# hvreg_feedback_2PS_FS.net
KiCad netlist of a schematic drawn in EAGLE
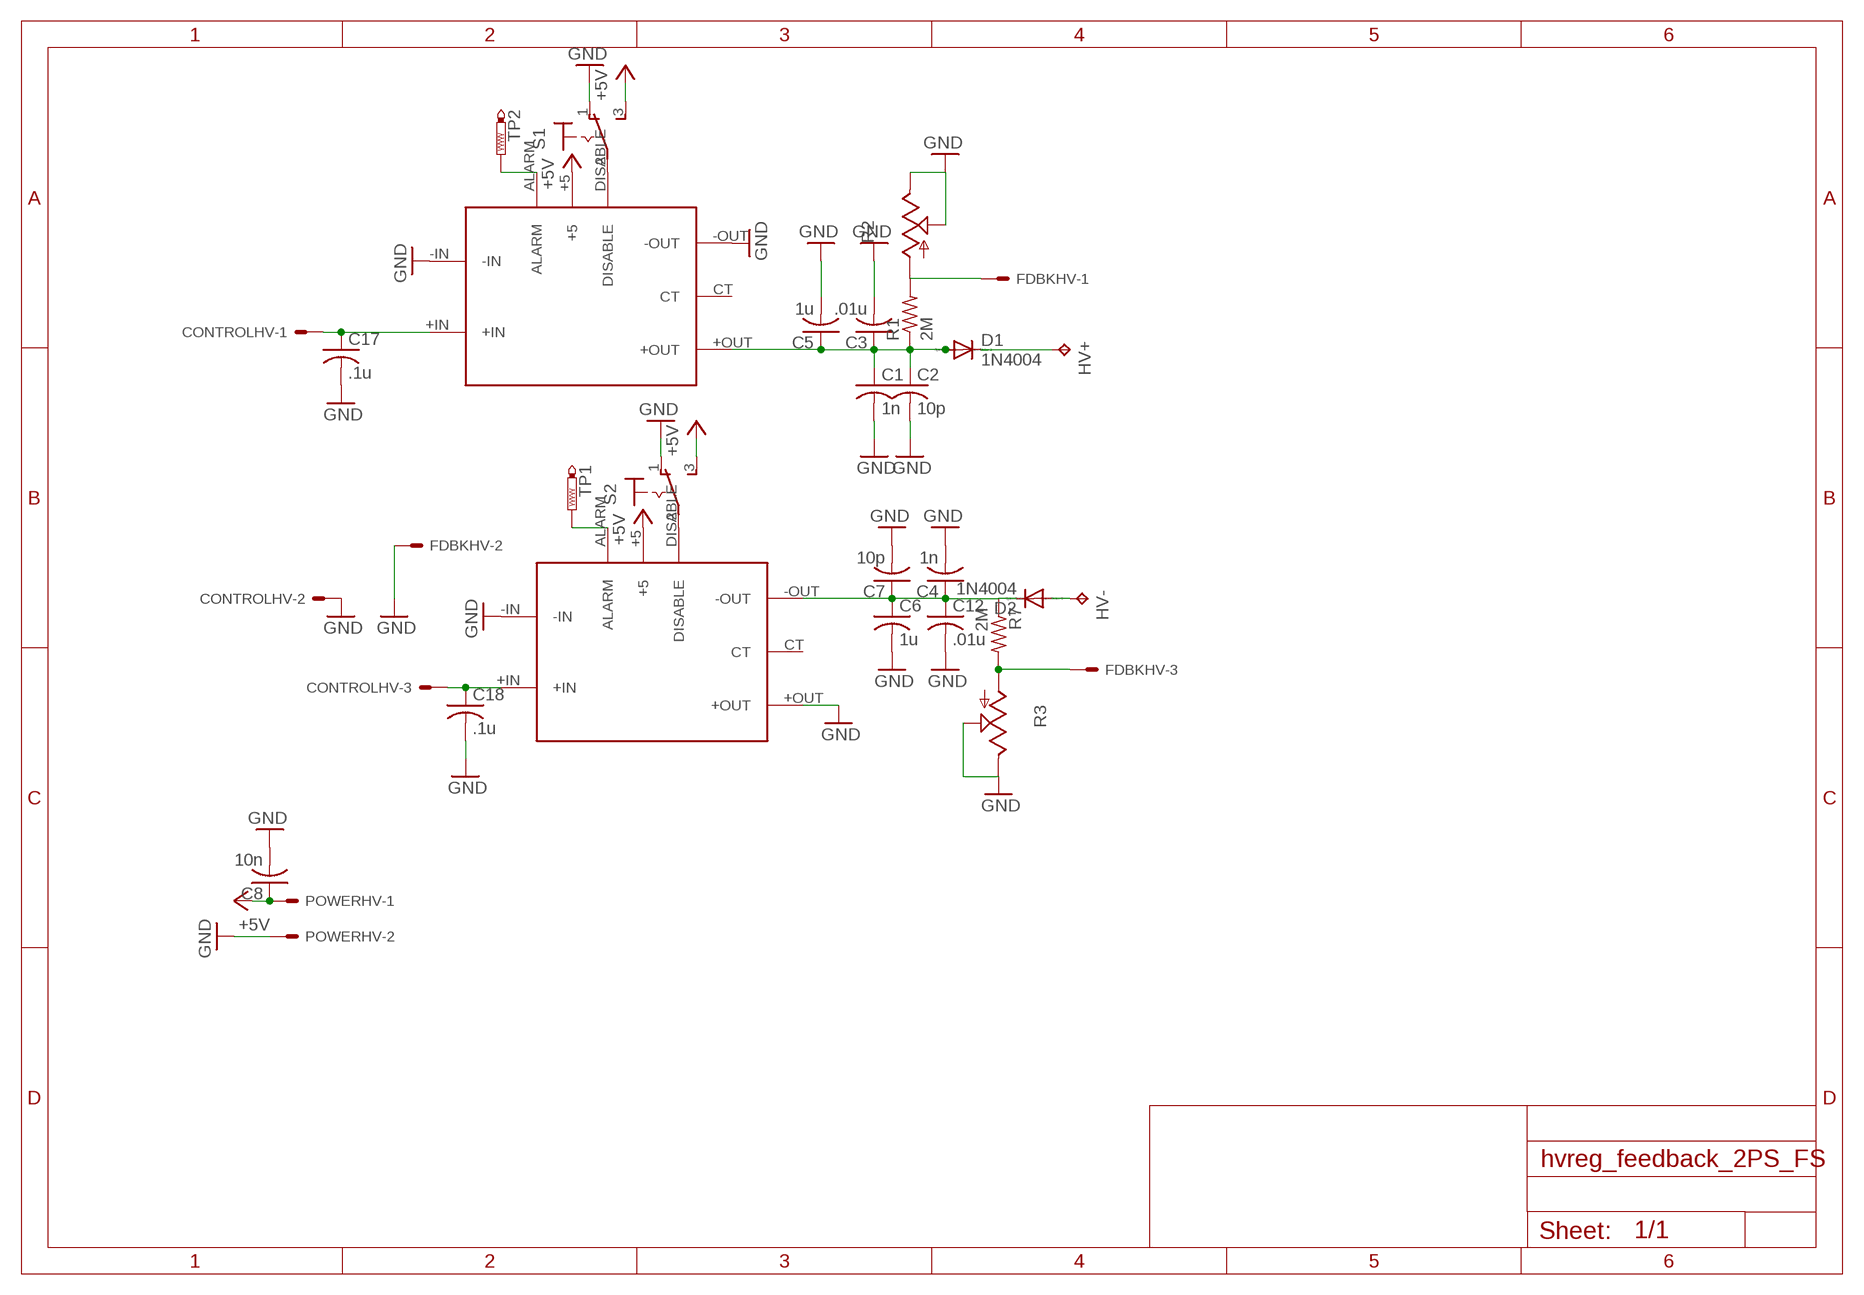
[diagram p0: schematic, sheet 1]

(export (version "E")
  (design (tool "Eeschema 10.0.6"))
  (components
    (comp (ref "C1")
      (value "1n")
      (footprint "eagle-import:C102-043X133")
      (libsource (lib "eagle-import") (part "C-US102-043X133"))
    )
    (comp (ref "C2")
      (value "10p")
      (footprint "eagle-import:C102-043X133")
      (libsource (lib "eagle-import") (part "C-US102-043X133"))
    )
    (comp (ref "C3")
      (value ".01u")
      (footprint "eagle-import:C102-043X133")
      (libsource (lib "eagle-import") (part "C-US102-043X133"))
    )
    (comp (ref "C4")
      (value "1n")
      (footprint "eagle-import:C102-043X133")
      (libsource (lib "eagle-import") (part "C-US102-043X133"))
    )
    (comp (ref "C5")
      (value "1u")
      (footprint "eagle-import:C275-205X316")
      (libsource (lib "eagle-import") (part "C-US275-205X316"))
    )
    (comp (ref "C6")
      (value "1u")
      (footprint "eagle-import:C275-205X316")
      (libsource (lib "eagle-import") (part "C-US275-205X316"))
    )
    (comp (ref "C7")
      (value "10p")
      (footprint "eagle-import:C102-043X133")
      (libsource (lib "eagle-import") (part "C-US102-043X133"))
    )
    (comp (ref "C8")
      (value "10n")
      (footprint "eagle-import:C050-024X044")
      (libsource (lib "eagle-import") (part "C-US050-024X044"))
    )
    (comp (ref "C12")
      (value ".01u")
      (footprint "eagle-import:C102-043X133")
      (libsource (lib "eagle-import") (part "C-US102-043X133"))
    )
    (comp (ref "C17")
      (value ".1u")
      (footprint "eagle-import:C225-113X268")
      (libsource (lib "eagle-import") (part "C-US225-113X268"))
    )
    (comp (ref "C18")
      (value ".1u")
      (footprint "eagle-import:C225-113X268")
      (libsource (lib "eagle-import") (part "C-US225-113X268"))
    )
    (comp (ref "CONTROLHV")
      (value "KK-156-3")
      (footprint "eagle-import:KK-156-3")
      (libsource (lib "eagle-import") (part "KK-156-3"))
    )
    (comp (ref "D1")
      (value "1N4004")
      (footprint "eagle-import:DO41-10")
      (libsource (lib "eagle-import") (part "1N4004"))
    )
    (comp (ref "D2")
      (value "1N4004")
      (footprint "eagle-import:DO41-10")
      (libsource (lib "eagle-import") (part "1N4004"))
    )
    (comp (ref "FDBKHV")
      (value "KK-156-3")
      (footprint "eagle-import:KK-156-3")
      (libsource (lib "eagle-import") (part "KK-156-3"))
    )
    (comp (ref "HV+")
      (value "TPPAD1-20Y")
      (footprint "eagle-import:P1-20Y")
      (libsource (lib "eagle-import") (part "TPPAD1-20Y"))
    )
    (comp (ref "HV-")
      (value "TPPAD1-20Y")
      (footprint "eagle-import:P1-20Y")
      (libsource (lib "eagle-import") (part "TPPAD1-20Y"))
    )
    (comp (ref "POWERHV")
      (value "KK-156-2")
      (footprint "eagle-import:KK-156-2")
      (libsource (lib "eagle-import") (part "KK-156-2"))
    )
    (comp (ref "R1")
      (value "2M")
      (footprint "eagle-import:P0613_15")
      (libsource (lib "eagle-import") (part "R-US_0613/15"))
    )
    (comp (ref "R2")
      (value "TRIM_US-B90P")
      (footprint "eagle-import:SP19L")
      (libsource (lib "eagle-import") (part "TRIM_US-B90P"))
    )
    (comp (ref "R3")
      (value "TRIM_US-B90P")
      (footprint "eagle-import:SP19L")
      (libsource (lib "eagle-import") (part "TRIM_US-B90P"))
    )
    (comp (ref "R7")
      (value "2M")
      (footprint "eagle-import:P0613_15")
      (libsource (lib "eagle-import") (part "R-US_0613/15"))
    )
    (comp (ref "S1")
      (value "M9040P")
      (footprint "eagle-import:M9040P")
      (libsource (lib "eagle-import") (part "M9040P"))
    )
    (comp (ref "S2")
      (value "M9040P")
      (footprint "eagle-import:M9040P")
      (libsource (lib "eagle-import") (part "M9040P"))
    )
    (comp (ref "TP1")
      (value "PTR1PAD1-20Y")
      (footprint "eagle-import:P1-20Y")
      (libsource (lib "eagle-import") (part "PTR1PAD1-20Y"))
    )
    (comp (ref "TP2")
      (value "PTR1PAD1-20Y")
      (footprint "eagle-import:P1-20Y")
      (libsource (lib "eagle-import") (part "PTR1PAD1-20Y"))
    )
    (comp (ref "U$1")
      (value "EMCO-FS10")
      (footprint "eagle-import:EMCO-FS")
      (libsource (lib "eagle-import") (part "EMCO-FS10"))
    )
    (comp (ref "U$2")
      (value "EMCO-FS10")
      (footprint "eagle-import:EMCO-FS")
      (libsource (lib "eagle-import") (part "EMCO-FS10"))
    )
  )
  (nets
    (net (code "1") (name "+5V") (class "Default")
      (node (ref "C8") (pin "1") (pinfunction "1_1") (pintype "passive"))
      (node (ref "POWERHV") (pin "1") (pinfunction "S_1") (pintype "passive"))
      (node (ref "S1") (pin "3") (pinfunction "S_3") (pintype "passive"))
      (node (ref "S2") (pin "3") (pinfunction "S_3") (pintype "passive"))
      (node (ref "U$1") (pin "+5") (pinfunction "+5_+5") (pintype "bidirectional"))
      (node (ref "U$2") (pin "+5") (pinfunction "+5_+5") (pintype "bidirectional"))
    )
    (net (code "2") (name "GND") (class "Default")
      (node (ref "C1") (pin "2") (pinfunction "2_2") (pintype "passive"))
      (node (ref "C12") (pin "2") (pinfunction "2_2") (pintype "passive"))
      (node (ref "C17") (pin "2") (pinfunction "2_2") (pintype "passive"))
      (node (ref "C18") (pin "2") (pinfunction "2_2") (pintype "passive"))
      (node (ref "C2") (pin "2") (pinfunction "2_2") (pintype "passive"))
      (node (ref "C3") (pin "2") (pinfunction "2_2") (pintype "passive"))
      (node (ref "C4") (pin "2") (pinfunction "2_2") (pintype "passive"))
      (node (ref "C5") (pin "2") (pinfunction "2_2") (pintype "passive"))
      (node (ref "C6") (pin "2") (pinfunction "2_2") (pintype "passive"))
      (node (ref "C7") (pin "2") (pinfunction "2_2") (pintype "passive"))
      (node (ref "C8") (pin "2") (pinfunction "2_2") (pintype "passive"))
      (node (ref "CONTROLHV") (pin "2") (pinfunction "S_2") (pintype "passive"))
      (node (ref "FDBKHV") (pin "2") (pinfunction "S_2") (pintype "passive"))
      (node (ref "POWERHV") (pin "2") (pinfunction "S_2") (pintype "passive"))
      (node (ref "R2") (pin "E") (pinfunction "E_E") (pintype "passive"))
      (node (ref "R2") (pin "S") (pinfunction "S_S") (pintype "passive"))
      (node (ref "R3") (pin "E") (pinfunction "E_E") (pintype "passive"))
      (node (ref "R3") (pin "S") (pinfunction "S_S") (pintype "passive"))
      (node (ref "S1") (pin "1") (pinfunction "O_1") (pintype "passive"))
      (node (ref "S2") (pin "1") (pinfunction "O_1") (pintype "passive"))
      (node (ref "U$1") (pin "-IN") (pinfunction "-IN_-IN") (pintype "bidirectional"))
      (node (ref "U$1") (pin "-OUT") (pinfunction "-OUT_-OUT") (pintype "bidirectional"))
      (node (ref "U$2") (pin "+OUT") (pinfunction "+OUT_+OUT") (pintype "bidirectional"))
      (node (ref "U$2") (pin "-IN") (pinfunction "-IN_-IN") (pintype "bidirectional"))
    )
    (net (code "3") (name "Net-(C1-Pad1)") (class "Default")
      (node (ref "C1") (pin "1") (pinfunction "1_1") (pintype "passive"))
      (node (ref "C2") (pin "1") (pinfunction "1_1") (pintype "passive"))
      (node (ref "C3") (pin "1") (pinfunction "1_1") (pintype "passive"))
      (node (ref "C5") (pin "1") (pinfunction "1_1") (pintype "passive"))
      (node (ref "D1") (pin "A") (pinfunction "A_A") (pintype "passive"))
      (node (ref "R1") (pin "1") (pinfunction "1_1") (pintype "passive"))
      (node (ref "U$1") (pin "+OUT") (pinfunction "+OUT_+OUT") (pintype "bidirectional"))
    )
    (net (code "4") (name "Net-(C12-Pad1)") (class "Default")
      (node (ref "C12") (pin "1") (pinfunction "1_1") (pintype "passive"))
      (node (ref "C4") (pin "1") (pinfunction "1_1") (pintype "passive"))
      (node (ref "C6") (pin "1") (pinfunction "1_1") (pintype "passive"))
      (node (ref "C7") (pin "1") (pinfunction "1_1") (pintype "passive"))
      (node (ref "D2") (pin "C") (pinfunction "C_C") (pintype "passive"))
      (node (ref "R7") (pin "1") (pinfunction "1_1") (pintype "passive"))
      (node (ref "U$2") (pin "-OUT") (pinfunction "-OUT_-OUT") (pintype "bidirectional"))
    )
    (net (code "5") (name "Net-(CONTROLHVA-S)") (class "Default")
      (node (ref "C17") (pin "1") (pinfunction "1_1") (pintype "passive"))
      (node (ref "CONTROLHV") (pin "1") (pinfunction "S_1") (pintype "passive"))
      (node (ref "U$1") (pin "+IN") (pinfunction "+IN_+IN") (pintype "bidirectional"))
    )
    (net (code "6") (name "Net-(CONTROLHVC-S)") (class "Default")
      (node (ref "C18") (pin "1") (pinfunction "1_1") (pintype "passive"))
      (node (ref "CONTROLHV") (pin "3") (pinfunction "S_3") (pintype "passive"))
      (node (ref "U$2") (pin "+IN") (pinfunction "+IN_+IN") (pintype "bidirectional"))
    )
    (net (code "7") (name "Net-(D1-PadC)") (class "Default")
      (node (ref "D1") (pin "C") (pinfunction "C_C") (pintype "passive"))
      (node (ref "HV+") (pin "TP") (pinfunction "TP_TP") (pintype "input"))
    )
    (net (code "8") (name "Net-(D2-PadA)") (class "Default")
      (node (ref "D2") (pin "A") (pinfunction "A_A") (pintype "passive"))
      (node (ref "HV-") (pin "TP") (pinfunction "TP_TP") (pintype "input"))
    )
    (net (code "9") (name "Net-(FDBKHVA-S)") (class "Default")
      (node (ref "FDBKHV") (pin "1") (pinfunction "S_1") (pintype "passive"))
      (node (ref "R1") (pin "2") (pinfunction "2_2") (pintype "passive"))
      (node (ref "R2") (pin "A") (pinfunction "A_A") (pintype "passive"))
    )
    (net (code "10") (name "Net-(FDBKHVC-S)") (class "Default")
      (node (ref "FDBKHV") (pin "3") (pinfunction "S_3") (pintype "passive"))
      (node (ref "R3") (pin "A") (pinfunction "A_A") (pintype "passive"))
      (node (ref "R7") (pin "2") (pinfunction "2_2") (pintype "passive"))
    )
    (net (code "11") (name "Net-(S1-P)") (class "Default")
      (node (ref "S1") (pin "2") (pinfunction "P_2") (pintype "passive"))
      (node (ref "U$1") (pin "DISABLE") (pinfunction "DISABLE_DISABLE") (pintype "bidirectional"))
    )
    (net (code "12") (name "Net-(S2-P)") (class "Default")
      (node (ref "S2") (pin "2") (pinfunction "P_2") (pintype "passive"))
      (node (ref "U$2") (pin "DISABLE") (pinfunction "DISABLE_DISABLE") (pintype "bidirectional"))
    )
    (net (code "13") (name "Net-(TP1-PadTP)") (class "Default")
      (node (ref "TP1") (pin "TP") (pinfunction "TP_TP") (pintype "input"))
      (node (ref "U$2") (pin "ALARM") (pinfunction "ALARM_ALARM") (pintype "bidirectional"))
    )
    (net (code "14") (name "Net-(TP2-PadTP)") (class "Default")
      (node (ref "TP2") (pin "TP") (pinfunction "TP_TP") (pintype "input"))
      (node (ref "U$1") (pin "ALARM") (pinfunction "ALARM_ALARM") (pintype "bidirectional"))
    )
    (net (code "15") (name "unconnected-(U$1-PadCT)") (class "Default")
      (node (ref "U$1") (pin "CT") (pinfunction "CT_CT") (pintype "bidirectional"))
    )
    (net (code "16") (name "unconnected-(U$2-PadCT)") (class "Default")
      (node (ref "U$2") (pin "CT") (pinfunction "CT_CT") (pintype "bidirectional"))
    )
  )
)
